# Short_SBUS_Hub.net
KiCad netlist of a schematic drawn in EAGLE
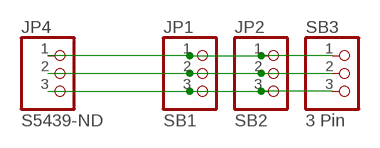
[diagram p0: schematic, sheet 1]

(export (version "E")
  (design (tool "Eeschema 10.0.6"))
  (components
    (comp (ref "JP1")
      (value "SB1")
      (footprint "eagle-import:1X03")
      (libsource (lib "eagle-import") (part "PINHD-1X3"))
    )
    (comp (ref "JP2")
      (value "SB2")
      (footprint "eagle-import:1X03")
      (libsource (lib "eagle-import") (part "PINHD-1X3"))
    )
    (comp (ref "JP4")
      (value "S5439-ND")
      (footprint "eagle-import:1X03")
      (libsource (lib "eagle-import") (part "PINHD-1X3"))
    )
    (comp (ref "SB3")
      (value "3 Pin")
      (footprint "eagle-import:1X03")
      (libsource (lib "eagle-import") (part "PINHD-1X3"))
    )
  )
  (nets
    (net (code "1") (name "Net-(JP1-Pad1)") (class "Default")
      (node (ref "JP1") (pin "1") (pinfunction "1_1") (pintype "passive"))
      (node (ref "JP2") (pin "1") (pinfunction "1_1") (pintype "passive"))
      (node (ref "JP4") (pin "1") (pinfunction "1_1") (pintype "passive"))
      (node (ref "SB3") (pin "1") (pinfunction "1_1") (pintype "passive"))
    )
    (net (code "2") (name "Net-(JP1-Pad2)") (class "Default")
      (node (ref "JP1") (pin "2") (pinfunction "2_2") (pintype "passive"))
      (node (ref "JP2") (pin "2") (pinfunction "2_2") (pintype "passive"))
      (node (ref "JP4") (pin "2") (pinfunction "2_2") (pintype "passive"))
      (node (ref "SB3") (pin "2") (pinfunction "2_2") (pintype "passive"))
    )
    (net (code "3") (name "Net-(JP1-Pad3)") (class "Default")
      (node (ref "JP1") (pin "3") (pinfunction "3_3") (pintype "passive"))
      (node (ref "JP2") (pin "3") (pinfunction "3_3") (pintype "passive"))
      (node (ref "JP4") (pin "3") (pinfunction "3_3") (pintype "passive"))
      (node (ref "SB3") (pin "3") (pinfunction "3_3") (pintype "passive"))
    )
  )
)
